# 5_led.net
KiCad netlist of a schematic drawn in Altium Designer
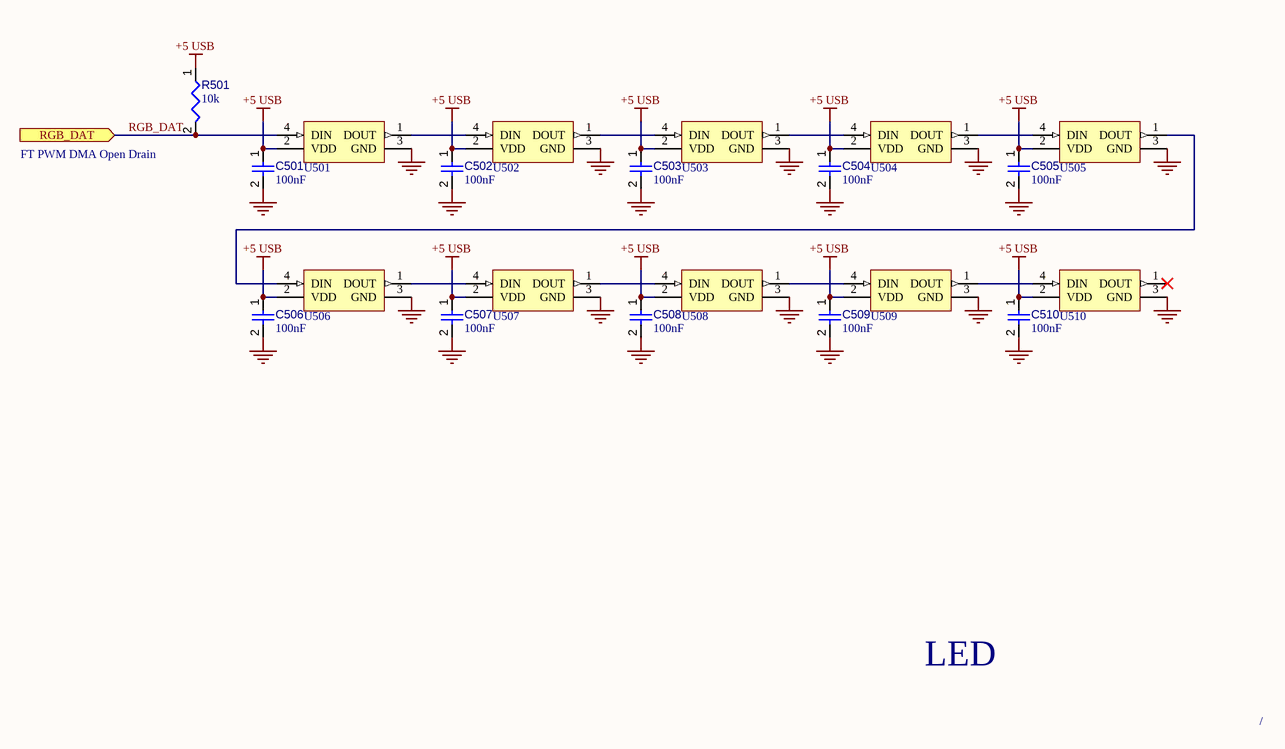
[diagram p0: 5 led.SchDoc]

(export (version "E")
  (design (tool "Eeschema 10.0.6"))
  (components
    (comp (ref "C501")
      (value "100nF")
      (footprint "CAPC0402(1005)60_L")
      (description "Chip Capacitor, 100nF +/-20%, 25V, 0402, Thickness 0.6 mm")
      (fields (field (name "TOLERANCE") "10%") (field (name "Comment") "Capacitor 100nF +/-20% 25V 0402"))
      (libsource (lib "UBC Uncrewed Aircraft Systems") (part "CAP-NP-2"))
    )
    (comp (ref "C502")
      (value "100nF")
      (footprint "CAPC0402(1005)60_L")
      (description "Chip Capacitor, 100nF +/-20%, 25V, 0402, Thickness 0.6 mm")
      (fields (field (name "TOLERANCE") "10%") (field (name "Comment") "Capacitor 100nF +/-20% 25V 0402"))
      (libsource (lib "UBC Uncrewed Aircraft Systems") (part "CAP-NP-2"))
    )
    (comp (ref "C503")
      (value "100nF")
      (footprint "CAPC0402(1005)60_L")
      (description "Chip Capacitor, 100nF +/-20%, 25V, 0402, Thickness 0.6 mm")
      (fields (field (name "TOLERANCE") "10%") (field (name "Comment") "Capacitor 100nF +/-20% 25V 0402"))
      (libsource (lib "UBC Uncrewed Aircraft Systems") (part "CAP-NP-2"))
    )
    (comp (ref "C504")
      (value "100nF")
      (footprint "CAPC0402(1005)60_L")
      (description "Chip Capacitor, 100nF +/-20%, 25V, 0402, Thickness 0.6 mm")
      (fields (field (name "TOLERANCE") "10%") (field (name "Comment") "Capacitor 100nF +/-20% 25V 0402"))
      (libsource (lib "UBC Uncrewed Aircraft Systems") (part "CAP-NP-2"))
    )
    (comp (ref "C505")
      (value "100nF")
      (footprint "CAPC0402(1005)60_L")
      (description "Chip Capacitor, 100nF +/-20%, 25V, 0402, Thickness 0.6 mm")
      (fields (field (name "TOLERANCE") "10%") (field (name "Comment") "Capacitor 100nF +/-20% 25V 0402"))
      (libsource (lib "UBC Uncrewed Aircraft Systems") (part "CAP-NP-2"))
    )
    (comp (ref "C506")
      (value "100nF")
      (footprint "CAPC0402(1005)60_L")
      (description "Chip Capacitor, 100nF +/-20%, 25V, 0402, Thickness 0.6 mm")
      (fields (field (name "TOLERANCE") "10%") (field (name "Comment") "Capacitor 100nF +/-20% 25V 0402"))
      (libsource (lib "UBC Uncrewed Aircraft Systems") (part "CAP-NP-2"))
    )
    (comp (ref "C507")
      (value "100nF")
      (footprint "CAPC0402(1005)60_L")
      (description "Chip Capacitor, 100nF +/-20%, 25V, 0402, Thickness 0.6 mm")
      (fields (field (name "TOLERANCE") "10%") (field (name "Comment") "Capacitor 100nF +/-20% 25V 0402"))
      (libsource (lib "UBC Uncrewed Aircraft Systems") (part "CAP-NP-2"))
    )
    (comp (ref "C508")
      (value "100nF")
      (footprint "CAPC0402(1005)60_L")
      (description "Chip Capacitor, 100nF +/-20%, 25V, 0402, Thickness 0.6 mm")
      (fields (field (name "TOLERANCE") "10%") (field (name "Comment") "Capacitor 100nF +/-20% 25V 0402"))
      (libsource (lib "UBC Uncrewed Aircraft Systems") (part "CAP-NP-2"))
    )
    (comp (ref "C509")
      (value "100nF")
      (footprint "CAPC0402(1005)60_L")
      (description "Chip Capacitor, 100nF +/-20%, 25V, 0402, Thickness 0.6 mm")
      (fields (field (name "TOLERANCE") "10%") (field (name "Comment") "Capacitor 100nF +/-20% 25V 0402"))
      (libsource (lib "UBC Uncrewed Aircraft Systems") (part "CAP-NP-2"))
    )
    (comp (ref "C510")
      (value "100nF")
      (footprint "CAPC0402(1005)60_L")
      (description "Chip Capacitor, 100nF +/-20%, 25V, 0402, Thickness 0.6 mm")
      (fields (field (name "TOLERANCE") "10%") (field (name "Comment") "Capacitor 100nF +/-20% 25V 0402"))
      (libsource (lib "UBC Uncrewed Aircraft Systems") (part "CAP-NP-2"))
    )
    (comp (ref "R501")
      (value "10k")
      (footprint "RESC0402(1005)_L")
      (description "Chip Resistor, 10 kOhms, +/-1 %, 63 mW, -55 to 125 degC, 0402")
      (fields (field (name "POWER") "63mW") (field (name "TOLERANCE") "1%"))
      (libsource (lib "UBC Uncrewed Aircraft Systems") (part "RES-2"))
    )
    (comp (ref "U501")
      (value "WS2812B 1615")
      (footprint "WS2812B 1615")
      (libsource (lib "JLCPCB Library") (part "WS2812B 1615"))
    )
    (comp (ref "U502")
      (value "WS2812B 1615")
      (footprint "WS2812B 1615")
      (libsource (lib "JLCPCB Library") (part "WS2812B 1615"))
    )
    (comp (ref "U503")
      (value "WS2812B 1615")
      (footprint "WS2812B 1615")
      (libsource (lib "JLCPCB Library") (part "WS2812B 1615"))
    )
    (comp (ref "U504")
      (value "WS2812B 1615")
      (footprint "WS2812B 1615")
      (libsource (lib "JLCPCB Library") (part "WS2812B 1615"))
    )
    (comp (ref "U505")
      (value "WS2812B 1615")
      (footprint "WS2812B 1615")
      (libsource (lib "JLCPCB Library") (part "WS2812B 1615"))
    )
    (comp (ref "U506")
      (value "WS2812B 1615")
      (footprint "WS2812B 1615")
      (libsource (lib "JLCPCB Library") (part "WS2812B 1615"))
    )
    (comp (ref "U507")
      (value "WS2812B 1615")
      (footprint "WS2812B 1615")
      (libsource (lib "JLCPCB Library") (part "WS2812B 1615"))
    )
    (comp (ref "U508")
      (value "WS2812B 1615")
      (footprint "WS2812B 1615")
      (libsource (lib "JLCPCB Library") (part "WS2812B 1615"))
    )
    (comp (ref "U509")
      (value "WS2812B 1615")
      (footprint "WS2812B 1615")
      (libsource (lib "JLCPCB Library") (part "WS2812B 1615"))
    )
    (comp (ref "U510")
      (value "WS2812B 1615")
      (footprint "WS2812B 1615")
      (libsource (lib "JLCPCB Library") (part "WS2812B 1615"))
    )
  )
  (nets
    (net (code "1") (name "+5 USB") (class "Default")
      (node (ref "C501") (pin "1") (pinfunction "1_1") (pintype "passive"))
      (node (ref "C502") (pin "1") (pinfunction "1_1") (pintype "passive"))
      (node (ref "C503") (pin "1") (pinfunction "1_1") (pintype "passive"))
      (node (ref "C504") (pin "1") (pinfunction "1_1") (pintype "passive"))
      (node (ref "C505") (pin "1") (pinfunction "1_1") (pintype "passive"))
      (node (ref "C506") (pin "1") (pinfunction "1_1") (pintype "passive"))
      (node (ref "C507") (pin "1") (pinfunction "1_1") (pintype "passive"))
      (node (ref "C508") (pin "1") (pinfunction "1_1") (pintype "passive"))
      (node (ref "C509") (pin "1") (pinfunction "1_1") (pintype "passive"))
      (node (ref "C510") (pin "1") (pinfunction "1_1") (pintype "passive"))
      (node (ref "R501") (pin "1") (pinfunction "1_1") (pintype "passive"))
      (node (ref "U501") (pin "2") (pinfunction "VDD_2") (pintype "power_in"))
      (node (ref "U502") (pin "2") (pinfunction "VDD_2") (pintype "power_in"))
      (node (ref "U503") (pin "2") (pinfunction "VDD_2") (pintype "power_in"))
      (node (ref "U504") (pin "2") (pinfunction "VDD_2") (pintype "power_in"))
      (node (ref "U505") (pin "2") (pinfunction "VDD_2") (pintype "power_in"))
      (node (ref "U506") (pin "2") (pinfunction "VDD_2") (pintype "power_in"))
      (node (ref "U507") (pin "2") (pinfunction "VDD_2") (pintype "power_in"))
      (node (ref "U508") (pin "2") (pinfunction "VDD_2") (pintype "power_in"))
      (node (ref "U509") (pin "2") (pinfunction "VDD_2") (pintype "power_in"))
      (node (ref "U510") (pin "2") (pinfunction "VDD_2") (pintype "power_in"))
    )
    (net (code "2") (name "/RGB_DAT") (class "Default")
      (node (ref "R501") (pin "2") (pinfunction "2_2") (pintype "passive"))
      (node (ref "U501") (pin "4") (pinfunction "DIN_4") (pintype "input"))
    )
    (net (code "3") (name "GND") (class "Default")
      (node (ref "C501") (pin "2") (pinfunction "2_2") (pintype "passive"))
      (node (ref "C502") (pin "2") (pinfunction "2_2") (pintype "passive"))
      (node (ref "C503") (pin "2") (pinfunction "2_2") (pintype "passive"))
      (node (ref "C504") (pin "2") (pinfunction "2_2") (pintype "passive"))
      (node (ref "C505") (pin "2") (pinfunction "2_2") (pintype "passive"))
      (node (ref "C506") (pin "2") (pinfunction "2_2") (pintype "passive"))
      (node (ref "C507") (pin "2") (pinfunction "2_2") (pintype "passive"))
      (node (ref "C508") (pin "2") (pinfunction "2_2") (pintype "passive"))
      (node (ref "C509") (pin "2") (pinfunction "2_2") (pintype "passive"))
      (node (ref "C510") (pin "2") (pinfunction "2_2") (pintype "passive"))
      (node (ref "U501") (pin "3") (pinfunction "GND_3") (pintype "power_in"))
      (node (ref "U502") (pin "3") (pinfunction "GND_3") (pintype "power_in"))
      (node (ref "U503") (pin "3") (pinfunction "GND_3") (pintype "power_in"))
      (node (ref "U504") (pin "3") (pinfunction "GND_3") (pintype "power_in"))
      (node (ref "U505") (pin "3") (pinfunction "GND_3") (pintype "power_in"))
      (node (ref "U506") (pin "3") (pinfunction "GND_3") (pintype "power_in"))
      (node (ref "U507") (pin "3") (pinfunction "GND_3") (pintype "power_in"))
      (node (ref "U508") (pin "3") (pinfunction "GND_3") (pintype "power_in"))
      (node (ref "U509") (pin "3") (pinfunction "GND_3") (pintype "power_in"))
      (node (ref "U510") (pin "3") (pinfunction "GND_3") (pintype "power_in"))
    )
    (net (code "4") (name "Net-(U501-DOUT)") (class "Default")
      (node (ref "U501") (pin "1") (pinfunction "DOUT_1") (pintype "output"))
      (node (ref "U502") (pin "4") (pinfunction "DIN_4") (pintype "input"))
    )
    (net (code "5") (name "Net-(U502-DOUT)") (class "Default")
      (node (ref "U502") (pin "1") (pinfunction "DOUT_1") (pintype "output"))
      (node (ref "U503") (pin "4") (pinfunction "DIN_4") (pintype "input"))
    )
    (net (code "6") (name "Net-(U503-DOUT)") (class "Default")
      (node (ref "U503") (pin "1") (pinfunction "DOUT_1") (pintype "output"))
      (node (ref "U504") (pin "4") (pinfunction "DIN_4") (pintype "input"))
    )
    (net (code "7") (name "Net-(U504-DOUT)") (class "Default")
      (node (ref "U504") (pin "1") (pinfunction "DOUT_1") (pintype "output"))
      (node (ref "U505") (pin "4") (pinfunction "DIN_4") (pintype "input"))
    )
    (net (code "8") (name "Net-(U505-DOUT)") (class "Default")
      (node (ref "U505") (pin "1") (pinfunction "DOUT_1") (pintype "output"))
      (node (ref "U506") (pin "4") (pinfunction "DIN_4") (pintype "input"))
    )
    (net (code "9") (name "Net-(U506-DOUT)") (class "Default")
      (node (ref "U506") (pin "1") (pinfunction "DOUT_1") (pintype "output"))
      (node (ref "U507") (pin "4") (pinfunction "DIN_4") (pintype "input"))
    )
    (net (code "10") (name "Net-(U507-DOUT)") (class "Default")
      (node (ref "U507") (pin "1") (pinfunction "DOUT_1") (pintype "output"))
      (node (ref "U508") (pin "4") (pinfunction "DIN_4") (pintype "input"))
    )
    (net (code "11") (name "Net-(U508-DOUT)") (class "Default")
      (node (ref "U508") (pin "1") (pinfunction "DOUT_1") (pintype "output"))
      (node (ref "U509") (pin "4") (pinfunction "DIN_4") (pintype "input"))
    )
    (net (code "12") (name "Net-(U509-DOUT)") (class "Default")
      (node (ref "U509") (pin "1") (pinfunction "DOUT_1") (pintype "output"))
      (node (ref "U510") (pin "4") (pinfunction "DIN_4") (pintype "input"))
    )
    (net (code "13") (name "unconnected-(U510-DOUT-Pad1)") (class "Default")
      (node (ref "U510") (pin "1") (pinfunction "DOUT_1") (pintype "output+no_connect"))
    )
  )
)
